# xSignals_1.net
KiCad netlist of a schematic drawn in Altium Designer
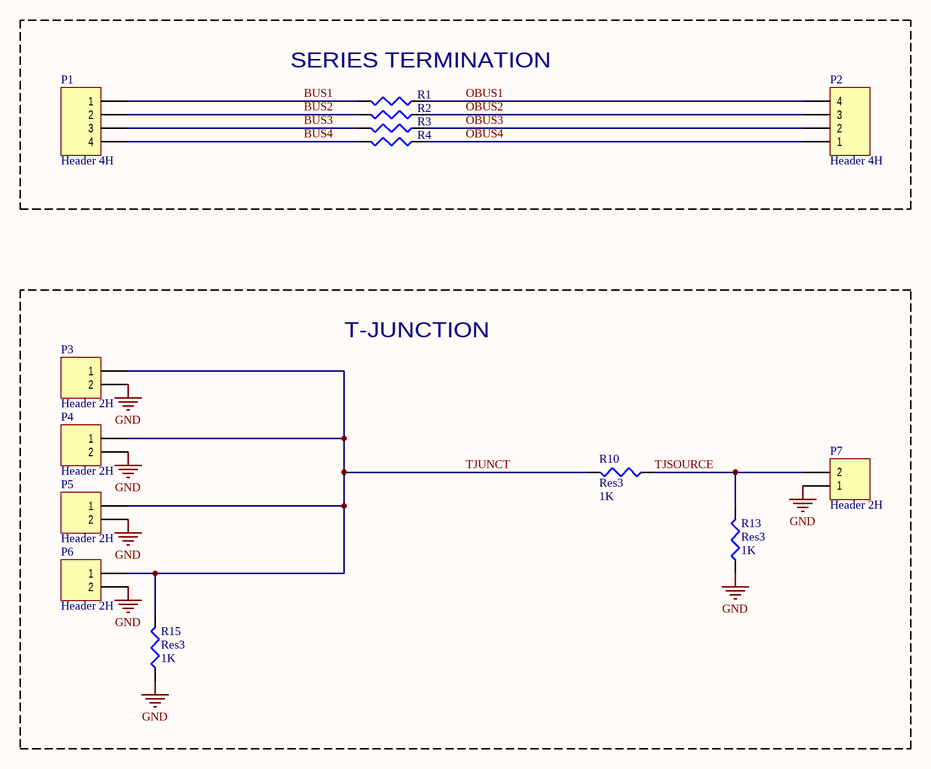
[diagram p0: xSignals(1).SchDoc]

(export (version "E")
  (design (tool "Eeschema 10.0.6"))
  (components
    (comp (ref "P1")
      (value "Header 4H")
      (footprint "HDR1X4H")
      (description "Header, 4-Pin, Right Angle")
      (fields (field (name "PUBLISHER") "Altium Limited"))
      (libsource (lib "Miscellaneous Connectors") (part "Header 4H"))
    )
    (comp (ref "P2")
      (value "Header 4H")
      (footprint "HDR1X4H")
      (description "Header, 4-Pin, Right Angle")
      (fields (field (name "PUBLISHER") "Altium Limited"))
      (libsource (lib "") (part "Header 4H_1"))
    )
    (comp (ref "P3")
      (value "Header 2H")
      (footprint "HDR1X2H")
      (description "Header, 2-Pin, Right Angle")
      (fields (field (name "PUBLISHER") "Altium Limited"))
      (libsource (lib "Miscellaneous Connectors") (part "Header 2H"))
    )
    (comp (ref "P4")
      (value "Header 2H")
      (footprint "HDR1X2H")
      (description "Header, 2-Pin, Right Angle")
      (fields (field (name "PUBLISHER") "Altium Limited"))
      (libsource (lib "Miscellaneous Connectors") (part "Header 2H"))
    )
    (comp (ref "P5")
      (value "Header 2H")
      (footprint "HDR1X2H")
      (description "Header, 2-Pin, Right Angle")
      (fields (field (name "PUBLISHER") "Altium Limited"))
      (libsource (lib "Miscellaneous Connectors") (part "Header 2H"))
    )
    (comp (ref "P6")
      (value "Header 2H")
      (footprint "HDR1X2H")
      (description "Header, 2-Pin, Right Angle")
      (fields (field (name "PUBLISHER") "Altium Limited"))
      (libsource (lib "Miscellaneous Connectors") (part "Header 2H"))
    )
    (comp (ref "P7")
      (value "Header 2H")
      (footprint "HDR1X2H")
      (description "Header, 2-Pin, Right Angle")
      (fields (field (name "PUBLISHER") "Altium Limited"))
      (libsource (lib "") (part "Header 2H_1"))
    )
    (comp (ref "R1")
      (value "Res3")
      (footprint "J1-0603")
      (description "Resistor")
      (fields (field (name "PUBLISHER") "Altium Limited"))
      (libsource (lib "Miscellaneous Devices") (part "Res3"))
    )
    (comp (ref "R2")
      (value "Res3")
      (footprint "J1-0603")
      (description "Resistor")
      (fields (field (name "PUBLISHER") "Altium Limited"))
      (libsource (lib "Miscellaneous Devices") (part "Res3"))
    )
    (comp (ref "R3")
      (value "Res3")
      (footprint "J1-0603")
      (description "Resistor")
      (fields (field (name "PUBLISHER") "Altium Limited"))
      (libsource (lib "Miscellaneous Devices") (part "Res3"))
    )
    (comp (ref "R4")
      (value "Res3")
      (footprint "J1-0603")
      (description "Resistor")
      (fields (field (name "PUBLISHER") "Altium Limited"))
      (libsource (lib "Miscellaneous Devices") (part "Res3"))
    )
    (comp (ref "R10")
      (value "Res3")
      (footprint "J1-0603")
      (description "Resistor")
      (fields (field (name "ALTIUM_VALUE") "1K") (field (name "PUBLISHER") "Altium Limited"))
      (libsource (lib "Miscellaneous Devices") (part "Res3"))
    )
    (comp (ref "R13")
      (value "Res3")
      (footprint "J1-0603")
      (description "Resistor")
      (fields (field (name "ALTIUM_VALUE") "1K") (field (name "PUBLISHER") "Altium Limited"))
      (libsource (lib "Miscellaneous Devices") (part "Res3"))
    )
    (comp (ref "R15")
      (value "Res3")
      (footprint "J1-0603")
      (description "Resistor")
      (fields (field (name "ALTIUM_VALUE") "1K") (field (name "PUBLISHER") "Altium Limited"))
      (libsource (lib "Miscellaneous Devices") (part "Res3"))
    )
  )
  (nets
    (net (code "1") (name "/BUS1") (class "Default")
      (node (ref "P1") (pin "1") (pinfunction "1_1") (pintype "passive"))
      (node (ref "R1") (pin "2") (pinfunction "2_2") (pintype "passive"))
    )
    (net (code "2") (name "/BUS2") (class "Default")
      (node (ref "P1") (pin "2") (pinfunction "2_2") (pintype "passive"))
      (node (ref "R2") (pin "2") (pinfunction "2_2") (pintype "passive"))
    )
    (net (code "3") (name "/BUS3") (class "Default")
      (node (ref "P1") (pin "3") (pinfunction "3_3") (pintype "passive"))
      (node (ref "R3") (pin "2") (pinfunction "2_2") (pintype "passive"))
    )
    (net (code "4") (name "/BUS4") (class "Default")
      (node (ref "P1") (pin "4") (pinfunction "4_4") (pintype "passive"))
      (node (ref "R4") (pin "2") (pinfunction "2_2") (pintype "passive"))
    )
    (net (code "5") (name "/OBUS1") (class "Default")
      (node (ref "P2") (pin "4") (pinfunction "4_4") (pintype "passive"))
      (node (ref "R1") (pin "1") (pinfunction "1_1") (pintype "passive"))
    )
    (net (code "6") (name "/OBUS2") (class "Default")
      (node (ref "P2") (pin "3") (pinfunction "3_3") (pintype "passive"))
      (node (ref "R2") (pin "1") (pinfunction "1_1") (pintype "passive"))
    )
    (net (code "7") (name "/OBUS3") (class "Default")
      (node (ref "P2") (pin "2") (pinfunction "2_2") (pintype "passive"))
      (node (ref "R3") (pin "1") (pinfunction "1_1") (pintype "passive"))
    )
    (net (code "8") (name "/OBUS4") (class "Default")
      (node (ref "P2") (pin "1") (pinfunction "1_1") (pintype "passive"))
      (node (ref "R4") (pin "1") (pinfunction "1_1") (pintype "passive"))
    )
    (net (code "9") (name "/TJSOURCE") (class "Default")
      (node (ref "P7") (pin "2") (pinfunction "2_2") (pintype "passive"))
      (node (ref "R10") (pin "1") (pinfunction "1_1") (pintype "passive"))
      (node (ref "R13") (pin "2") (pinfunction "2_2") (pintype "passive"))
    )
    (net (code "10") (name "/TJUNCT") (class "Default")
      (node (ref "P3") (pin "1") (pinfunction "1_1") (pintype "passive"))
      (node (ref "P4") (pin "1") (pinfunction "1_1") (pintype "passive"))
      (node (ref "P5") (pin "1") (pinfunction "1_1") (pintype "passive"))
      (node (ref "P6") (pin "1") (pinfunction "1_1") (pintype "passive"))
      (node (ref "R10") (pin "2") (pinfunction "2_2") (pintype "passive"))
      (node (ref "R15") (pin "2") (pinfunction "2_2") (pintype "passive"))
    )
    (net (code "11") (name "GND") (class "Default")
      (node (ref "P3") (pin "2") (pinfunction "2_2") (pintype "passive"))
      (node (ref "P4") (pin "2") (pinfunction "2_2") (pintype "passive"))
      (node (ref "P5") (pin "2") (pinfunction "2_2") (pintype "passive"))
      (node (ref "P6") (pin "2") (pinfunction "2_2") (pintype "passive"))
      (node (ref "P7") (pin "1") (pinfunction "1_1") (pintype "passive"))
      (node (ref "R13") (pin "1") (pinfunction "1_1") (pintype "passive"))
      (node (ref "R15") (pin "1") (pinfunction "1_1") (pintype "passive"))
    )
  )
)
